# 09_Buzzer.net
KiCad netlist of a schematic drawn in Altium Designer
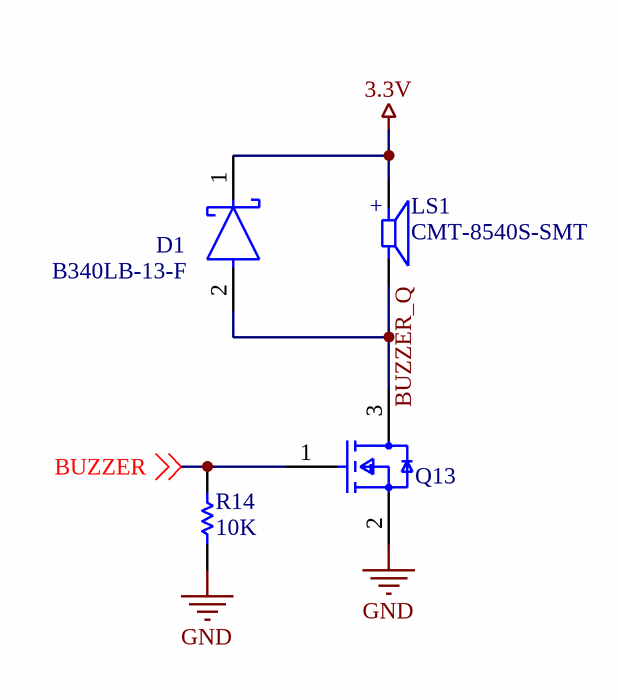
[diagram p0: 09_Buzzer.SchDoc]

(export (version "E")
  (design (tool "Eeschema 10.0.6"))
  (components
    (comp (ref "D1")
      (value "B340LB-13-F")
      (footprint "FP-SMB-MFG")
      (description "DIODE SCHOTTKY 40V 3A SMB")
      (fields
        (field (name "OCTOPART") "https://octopart.com/b340lb-13-f-diodes+inc.-325823")
        (field (name "MANUFACTURER") "Diodes Inc.")
      )
      (libsource (lib "Altium Content Vault") (part "1d6ec82d83fb6aee721767c19dac4b9"))
    )
    (comp (ref "LS1")
      (value "CMT-8540S-SMT")
      (footprint "CUI_CMT-8540S-SMT")
      (description "AUDIO MAGNETIC XDCR 1-6V SMD")
      (fields (field (name "MF") "CUI Devices") (field (name "MP") "CMT-8540S-SMT-TR"))
      (libsource (lib "ECE315") (part "CMT-8540S-SMT"))
    )
    (comp (ref "Q13")
      (value "2N7002-7-F")
      (footprint "FP-SOT23-MFG")
      (description "MOSFET N-CH 60V 115MA SOT23-3")
      (fields (field (name "VOLTAGE") "60V"))
      (libsource (lib "Altium Content Vault") (part "3b9c635fedb024a5347a57b145af9cc"))
    )
    (comp (ref "R14")
      (value "RC1206FR-0710KL")
      (footprint "RESC3116X65X40ML10T20")
      (description "Chip Resistor, 10 KOhm, +/- 1%, 0.25 W, -55 to 155 degC, 1206 (3216 Metric), RoHS, Tape and Reel")
      (fields
        (field (name "TOLERANCE") "1%")
        (field (name "RESISTANCE") "10K")
        (field (name "MANUFACTURER") "Yageo")
      )
      (libsource (lib "Altium Content Vault") (part "RES-2"))
    )
  )
  (nets
    (net (code "1") (name "/BUZZER_Q") (class "Default")
      (node (ref "D1") (pin "2") (pinfunction "A_2") (pintype "passive"))
      (node (ref "LS1") (pin "N") (pinfunction "N_N") (pintype "passive"))
      (node (ref "Q13") (pin "3") (pinfunction "D_3") (pintype "passive"))
    )
    (net (code "2") (name "3.3V") (class "Default")
      (node (ref "D1") (pin "1") (pinfunction "C_1") (pintype "passive"))
      (node (ref "LS1") (pin "P") (pinfunction "P_P") (pintype "passive"))
    )
    (net (code "3") (name "BUZZER") (class "Default")
      (node (ref "Q13") (pin "1") (pinfunction "G_1") (pintype "passive"))
      (node (ref "R14") (pin "2") (pinfunction "2_2") (pintype "passive"))
    )
    (net (code "4") (name "GND") (class "Default")
      (node (ref "Q13") (pin "2") (pinfunction "S_2") (pintype "passive"))
      (node (ref "R14") (pin "1") (pinfunction "1_1") (pintype "passive"))
    )
  )
)
